# SCH_NFC_card_2024-08-10.net
KiCad netlist of a schematic drawn in EasyEDA
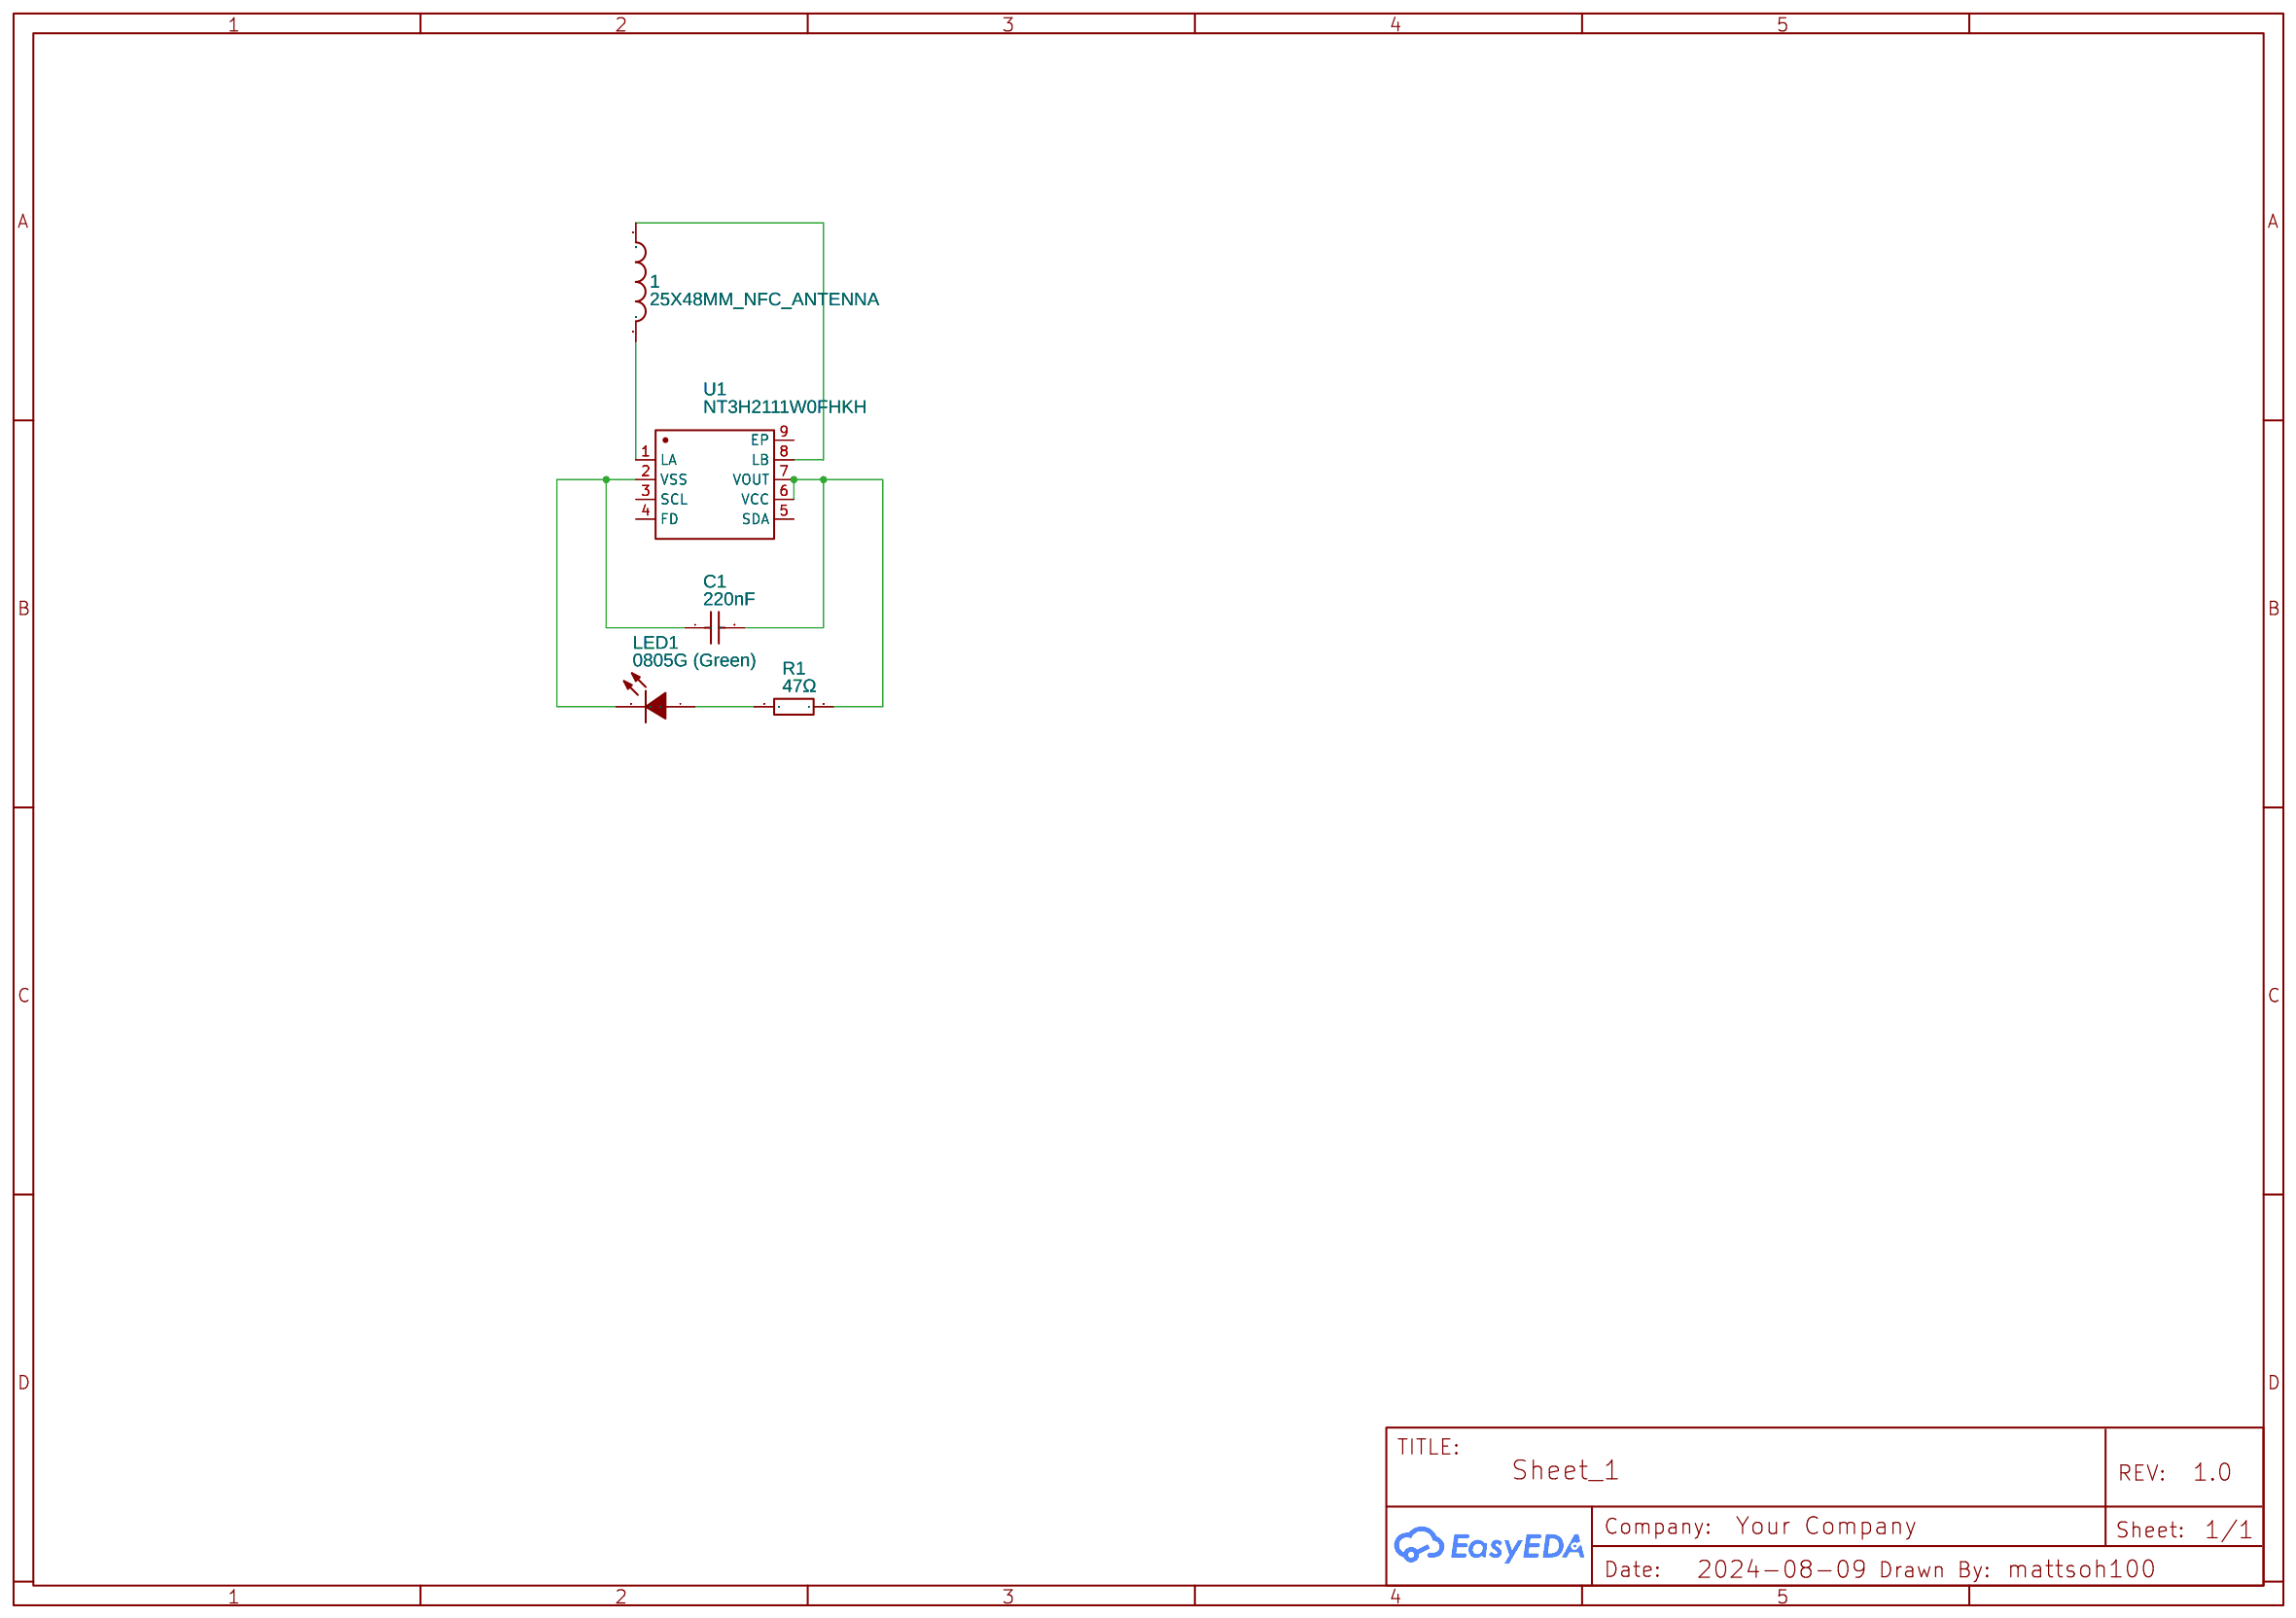
[diagram p0: schematic sheet]

(export (version "E")
  (design (tool "Eeschema 10.0.6"))
  (components
    (comp (ref "1") (value "25X48MM_NFC_ANTENNA") (libsource (lib "") (part "25X48MM_NFC_ANTENNA")))
    (comp (ref "C1")
      (value "220nF")
      (fields
        (field (name "Manufacturer Part") "CL10B224KA8NNNC")
        (field (name "Manufacturer") "SAMSUNG(三星)")
      )
      (libsource (lib "") (part "CL10B224KA8NNNC"))
    )
    (comp (ref "LED1")
      (value "0805G (Green)")
      (fields (field (name "Manufacturer Part") "KT-0805G") (field (name "Manufacturer") "KENTO"))
      (libsource (lib "") (part "0805G (Green)"))
    )
    (comp (ref "R1")
      (value "47Ω")
      (fields
        (field (name "Manufacturer Part") "0603WAF470JT5E")
        (field (name "Manufacturer") "UNI-ROYAL(厚声)")
      )
      (libsource (lib "") (part "0603WAF470JT5E"))
    )
    (comp (ref "U1")
      (value "NT3H2111W0FHKH")
      (fields (field (name "Manufacturer") "NXP(恩智浦)"))
      (libsource (lib "") (part "NT3H2111W0FHKH"))
    )
  )
  (nets
    (net (code "1") (name "Net-(LED1-A)") (class "Default")
      (node (ref "LED1") (pin "1") (pinfunction "A_1") (pintype "unspecified"))
      (node (ref "R1") (pin "1") (pinfunction "1_1") (pintype "input"))
    )
    (net (code "2") (name "Net-(LED1-K)") (class "Default")
      (node (ref "C1") (pin "1") (pinfunction "1_1") (pintype "input"))
      (node (ref "LED1") (pin "2") (pinfunction "K_2") (pintype "unspecified"))
      (node (ref "U1") (pin "2") (pinfunction "VSS_2") (pintype "unspecified"))
    )
    (net (code "3") (name "Net-(U1-LA)") (class "Default")
      (node (ref "1") (pin "P$2") (pinfunction "P$2_P$2") (pintype "bidirectional"))
      (node (ref "U1") (pin "1") (pinfunction "LA_1") (pintype "unspecified"))
    )
    (net (code "4") (name "Net-(U1-LB)") (class "Default")
      (node (ref "1") (pin "P$1") (pinfunction "P$1_P$1") (pintype "bidirectional"))
      (node (ref "U1") (pin "8") (pinfunction "LB_8") (pintype "unspecified"))
    )
    (net (code "5") (name "Net-(U1-VCC)") (class "Default")
      (node (ref "C1") (pin "2") (pinfunction "2_2") (pintype "input"))
      (node (ref "R1") (pin "2") (pinfunction "2_2") (pintype "input"))
      (node (ref "U1") (pin "6") (pinfunction "VCC_6") (pintype "unspecified"))
      (node (ref "U1") (pin "7") (pinfunction "VOUT_7") (pintype "unspecified"))
    )
    (net (code "6") (name "unconnected-(U1-EP-Pad9)") (class "Default")
      (node (ref "U1") (pin "9") (pinfunction "EP_9") (pintype "unspecified"))
    )
    (net (code "7") (name "unconnected-(U1-FD-Pad4)") (class "Default")
      (node (ref "U1") (pin "4") (pinfunction "FD_4") (pintype "unspecified"))
    )
    (net (code "8") (name "unconnected-(U1-SCL-Pad3)") (class "Default")
      (node (ref "U1") (pin "3") (pinfunction "SCL_3") (pintype "unspecified"))
    )
    (net (code "9") (name "unconnected-(U1-SDA-Pad5)") (class "Default")
      (node (ref "U1") (pin "5") (pinfunction "SDA_5") (pintype "unspecified"))
    )
  )
)
